# CANBed2040_V1_1.net
KiCad netlist of a schematic drawn in EAGLE
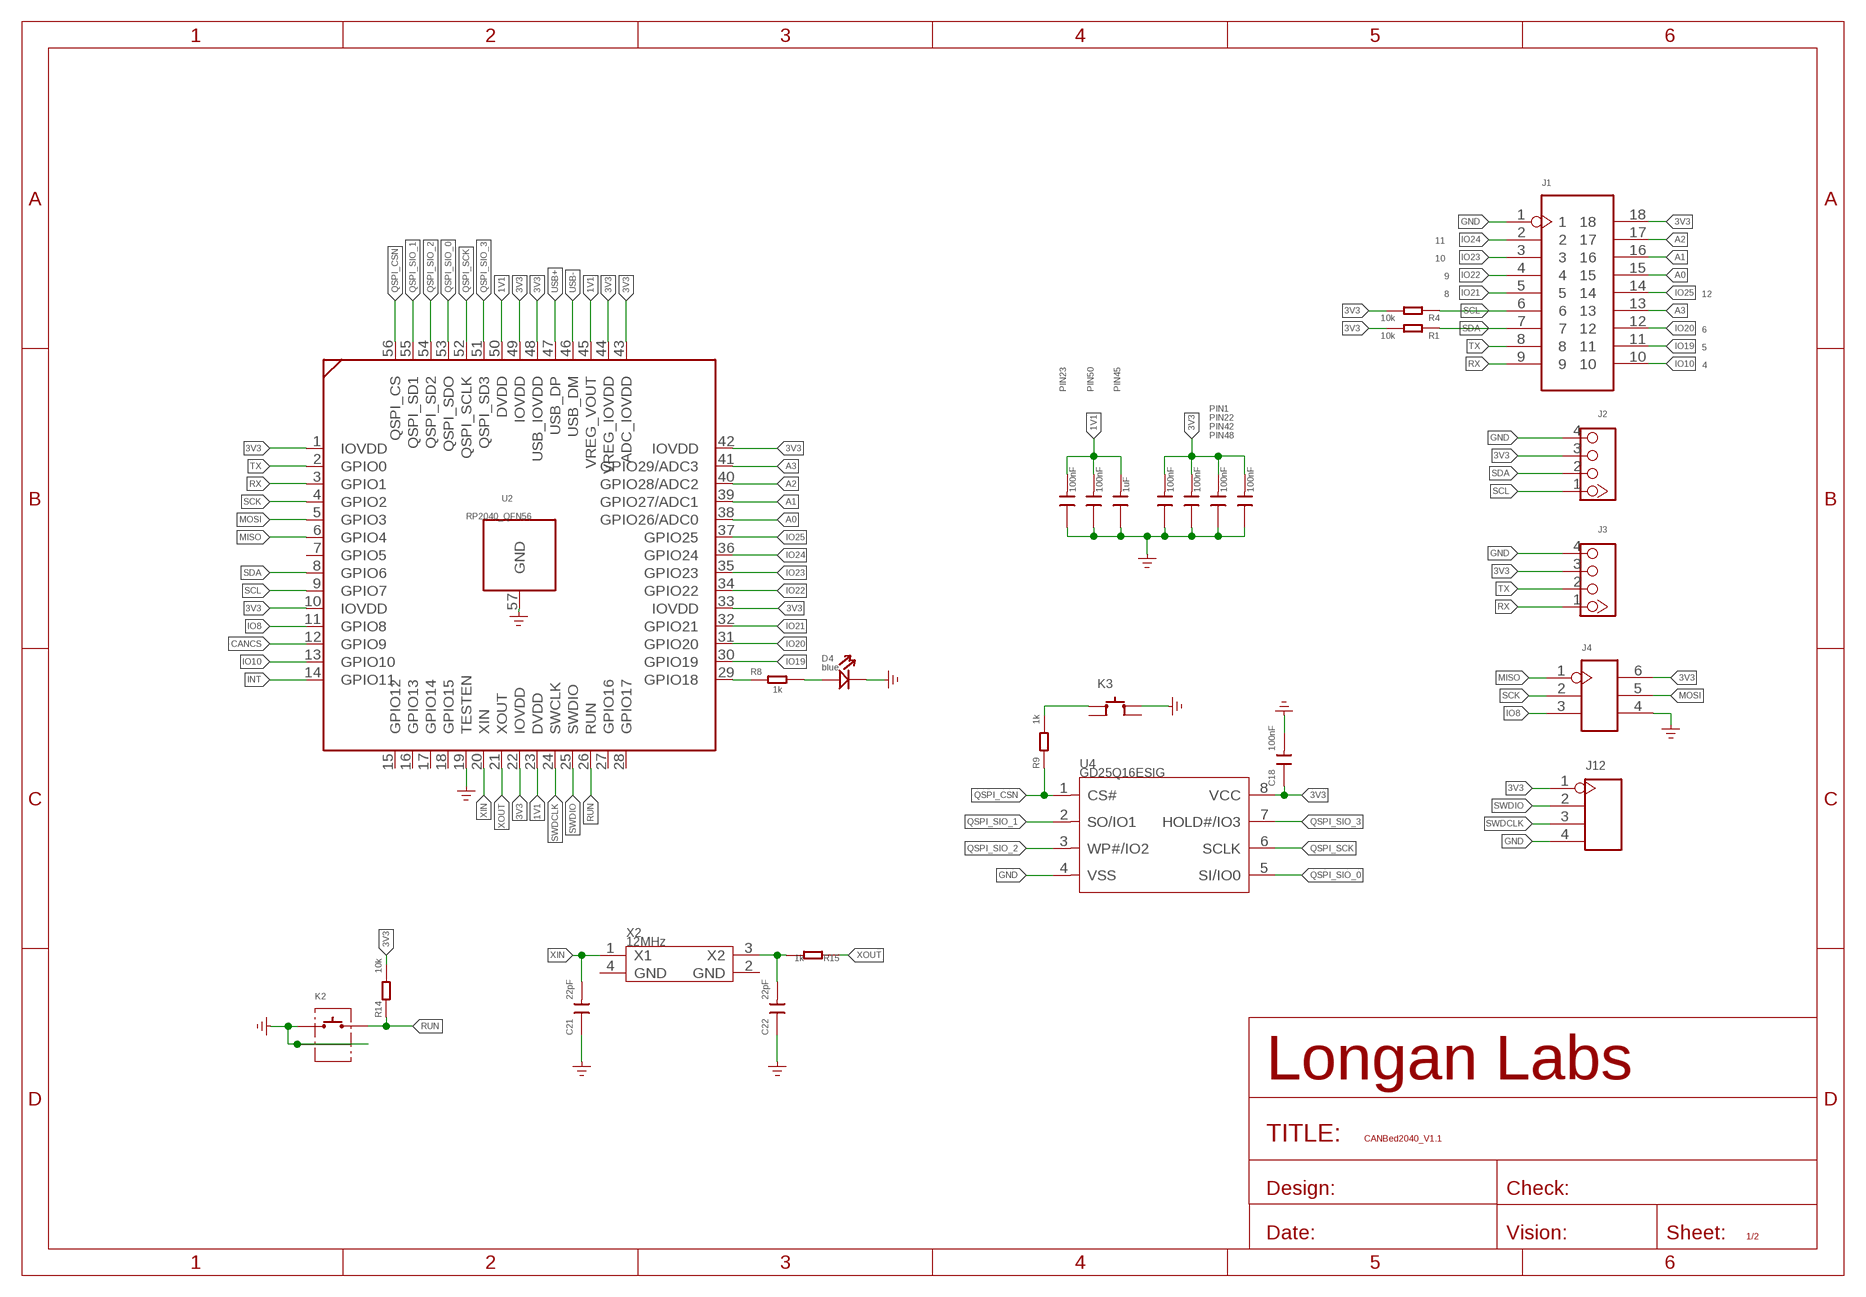
[diagram p0: schematic, sheet 1, part 1 of 2]
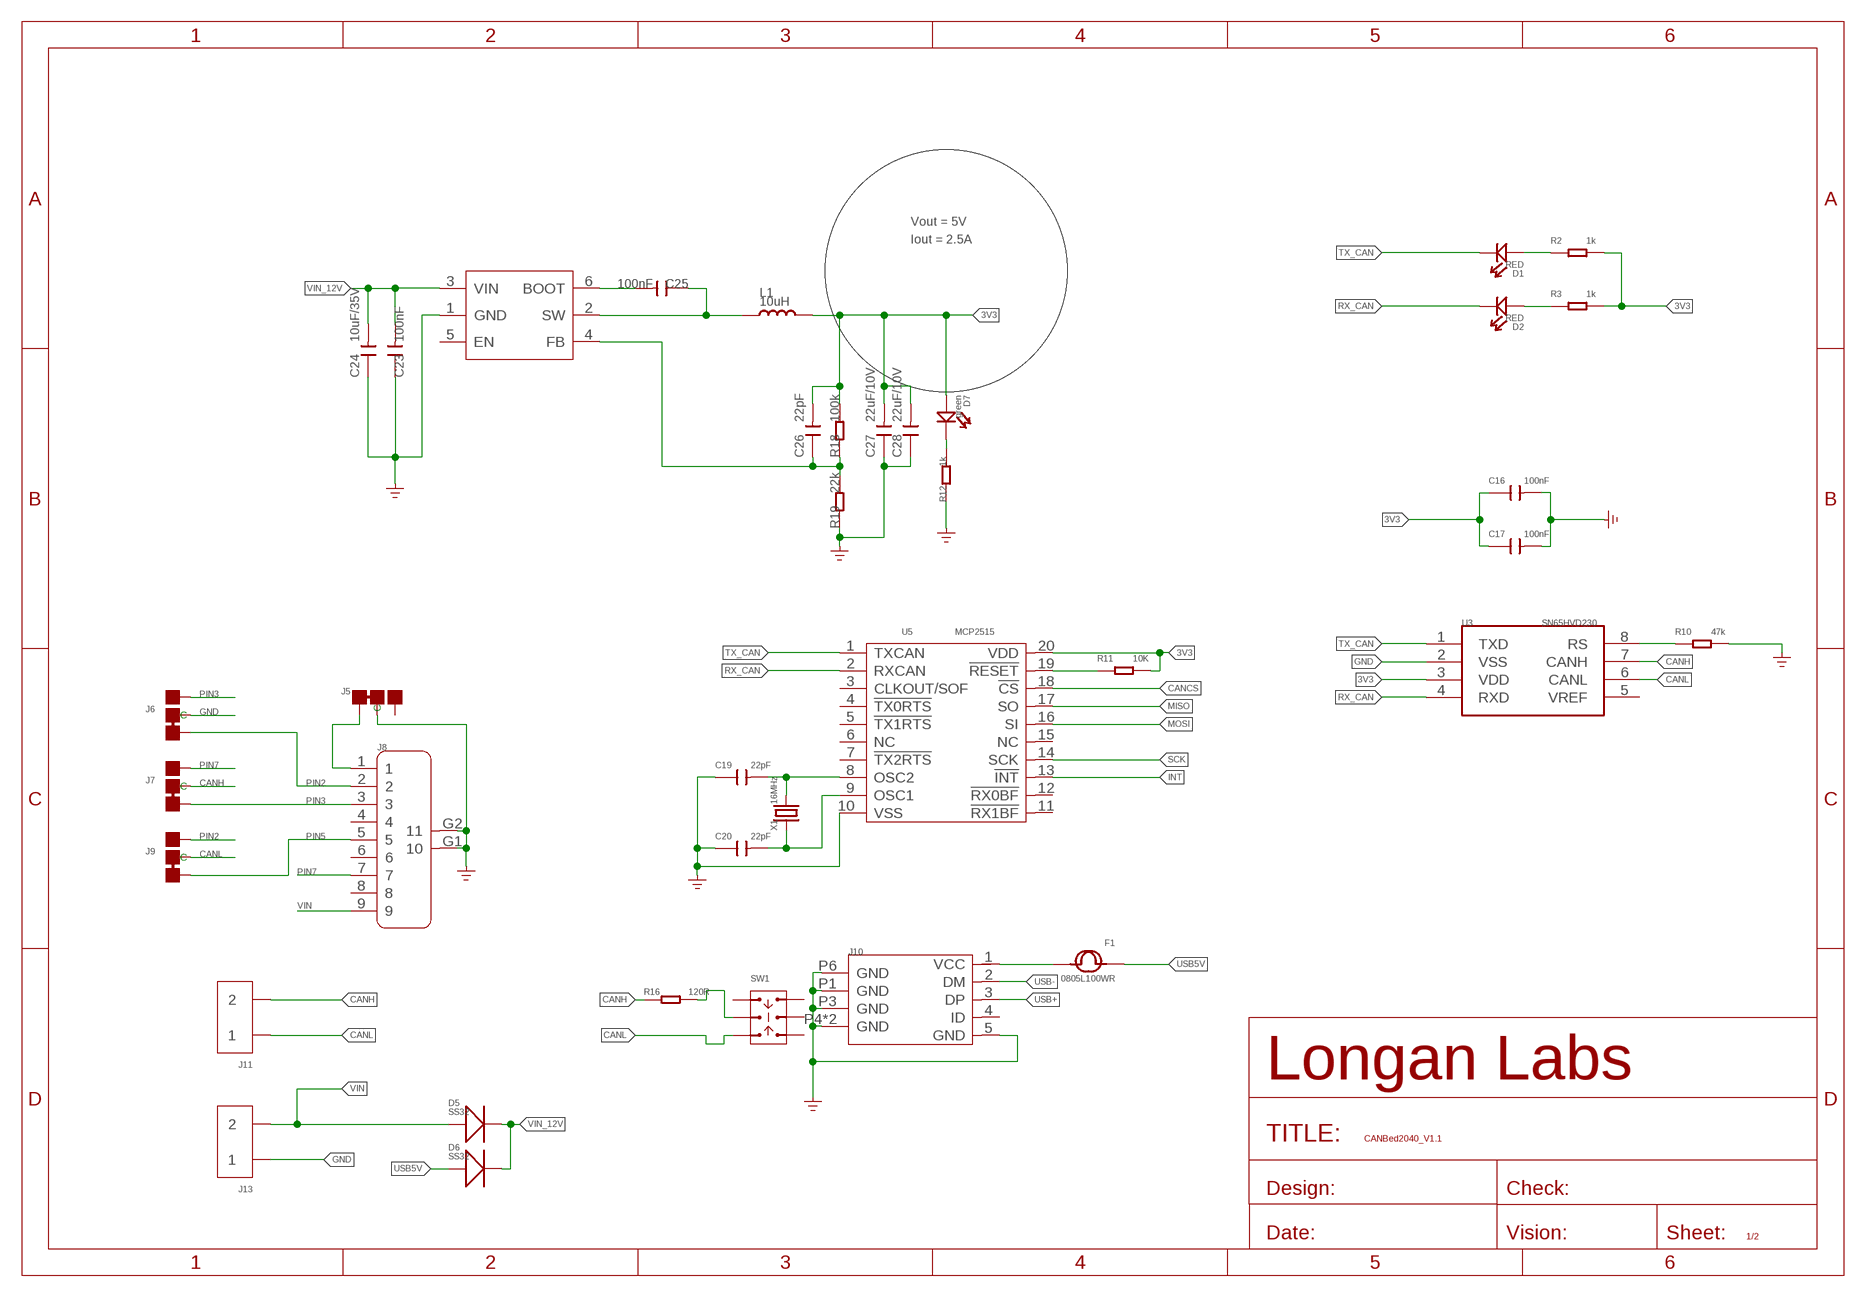
[diagram p1: schematic, sheet 1, part 2 of 2]

(export (version "E")
  (design (tool "Eeschema 10.0.6"))
  (components
    (comp (ref "C9")
      (value "100nF")
      (footprint "eagle-import:C0603")
      (libsource (lib "eagle-import") (part "CAP-0603"))
    )
    (comp (ref "C10")
      (value "100nF")
      (footprint "eagle-import:C0603")
      (libsource (lib "eagle-import") (part "CAP-0603"))
    )
    (comp (ref "C11")
      (value "1uF")
      (footprint "eagle-import:C0603")
      (libsource (lib "eagle-import") (part "CAP-0603"))
    )
    (comp (ref "C12")
      (value "100nF")
      (footprint "eagle-import:C0603")
      (libsource (lib "eagle-import") (part "CAP-0603"))
    )
    (comp (ref "C13")
      (value "100nF")
      (footprint "eagle-import:C0603")
      (libsource (lib "eagle-import") (part "CAP-0603"))
    )
    (comp (ref "C14")
      (value "100nF")
      (footprint "eagle-import:C0603")
      (libsource (lib "eagle-import") (part "CAP-0603"))
    )
    (comp (ref "C15")
      (value "100nF")
      (footprint "eagle-import:C0603")
      (libsource (lib "eagle-import") (part "CAP-0603"))
    )
    (comp (ref "C16")
      (value "100nF")
      (footprint "eagle-import:C0603")
      (libsource (lib "eagle-import") (part "CAP-0603"))
    )
    (comp (ref "C17")
      (value "100nF")
      (footprint "eagle-import:C0603")
      (libsource (lib "eagle-import") (part "CAP-0603"))
    )
    (comp (ref "C18")
      (value "100nF")
      (footprint "eagle-import:C0603")
      (libsource (lib "eagle-import") (part "CAP-0603"))
    )
    (comp (ref "C19")
      (value "22pF")
      (footprint "eagle-import:C0603")
      (libsource (lib "eagle-import") (part "CAP-0603"))
    )
    (comp (ref "C20")
      (value "22pF")
      (footprint "eagle-import:C0603")
      (libsource (lib "eagle-import") (part "CAP-0603"))
    )
    (comp (ref "C21")
      (value "22pF")
      (footprint "eagle-import:C0603")
      (libsource (lib "eagle-import") (part "CAP-0603"))
    )
    (comp (ref "C22")
      (value "22pF")
      (footprint "eagle-import:C0603")
      (libsource (lib "eagle-import") (part "CAP-0603"))
    )
    (comp (ref "C23")
      (value "100nF")
      (footprint "eagle-import:C0603")
      (libsource (lib "eagle-import") (part "CAP-0603"))
    )
    (comp (ref "C24")
      (value "10uF/35V")
      (footprint "eagle-import:C1206")
      (libsource (lib "eagle-import") (part "CAP-1206"))
    )
    (comp (ref "C25")
      (value "100nF")
      (footprint "eagle-import:C0603")
      (libsource (lib "eagle-import") (part "CAP-0603"))
    )
    (comp (ref "C26")
      (value "22pF")
      (footprint "eagle-import:C0603")
      (libsource (lib "eagle-import") (part "CAP-0603"))
    )
    (comp (ref "C27")
      (value "22uF/10V")
      (footprint "eagle-import:C0805")
      (libsource (lib "eagle-import") (part "CAP-0805"))
    )
    (comp (ref "C28")
      (value "22uF/10V")
      (footprint "eagle-import:C0805")
      (libsource (lib "eagle-import") (part "CAP-0805"))
    )
    (comp (ref "D1")
      (value "RED")
      (footprint "eagle-import:LED-0603")
      (libsource (lib "eagle-import") (part "LED'0603'"))
    )
    (comp (ref "D2")
      (value "RED")
      (footprint "eagle-import:LED-0603")
      (libsource (lib "eagle-import") (part "LED'0603'"))
    )
    (comp (ref "D4")
      (value "blue")
      (footprint "eagle-import:LED-0603")
      (libsource (lib "eagle-import") (part "LED'0603'"))
    )
    (comp (ref "D5")
      (value "SS32")
      (footprint "eagle-import:DO-214AC")
      (libsource (lib "eagle-import") (part "DIODE'SMA'"))
    )
    (comp (ref "D6")
      (value "SS32")
      (footprint "eagle-import:DO-214AC")
      (libsource (lib "eagle-import") (part "DIODE'SMA'"))
    )
    (comp (ref "D7")
      (value "green")
      (footprint "eagle-import:LED-0603")
      (libsource (lib "eagle-import") (part "LED'0603'"))
    )
    (comp (ref "F1")
      (value "0805L100WR")
      (footprint "eagle-import:F0805")
      (libsource (lib "eagle-import") (part "FUSE0805"))
    )
    (comp (ref "J1")
      (value "HEADER-2X9P-2.54")
      (footprint "eagle-import:H2X9-2.54")
      (libsource (lib "eagle-import") (part "HEADER-2X9P-2.54"))
    )
    (comp (ref "J2")
      (value "320110033")
      (footprint "eagle-import:HW4-2.0")
      (libsource (lib "eagle-import") (part "GROVE-CONNECTOR-DIP-2.0"))
    )
    (comp (ref "J3")
      (value "320110033")
      (footprint "eagle-import:HW4-2.0")
      (libsource (lib "eagle-import") (part "GROVE-CONNECTOR-DIP-2.0"))
    )
    (comp (ref "J4")
      (value "HEADER-2X3P-2.54")
      (footprint "eagle-import:H2X3-2.54")
      (libsource (lib "eagle-import") (part "HEADER-2X3P-2.54"))
    )
    (comp (ref "J5")
      (value "JUMPER-3P-SHORT")
      (footprint "eagle-import:3P-SMD-SHORT")
      (libsource (lib "eagle-import") (part "JUMPER-3P-SHORT"))
    )
    (comp (ref "J6")
      (value "JUMPER-3P-SHORT")
      (footprint "eagle-import:3P-SMD-SHORT")
      (libsource (lib "eagle-import") (part "JUMPER-3P-SHORT"))
    )
    (comp (ref "J7")
      (value "JUMPER-3P-SHORT")
      (footprint "eagle-import:3P-SMD-SHORT")
      (libsource (lib "eagle-import") (part "JUMPER-3P-SHORT"))
    )
    (comp (ref "J8")
      (value "DB9'MEAL'")
      (footprint "eagle-import:DB9-MEAL")
      (libsource (lib "eagle-import") (part "DB9'MEAL'"))
    )
    (comp (ref "J9")
      (value "JUMPER-3P-SHORT")
      (footprint "eagle-import:3P-SMD-SHORT")
      (libsource (lib "eagle-import") (part "JUMPER-3P-SHORT"))
    )
    (comp (ref "J10")
      (value "MICRO-USB5+4P-320010050")
      (footprint "eagle-import:MICRO-USB5+5P-SMD-0.65-7.2X5.06MM")
      (libsource (lib "eagle-import") (part "MICRO-USB5+4P-320010050"))
    )
    (comp (ref "J11")
      (value "SCREW-TERMINAL-2P'5.08'")
      (footprint "eagle-import:H2-5.0-10.5X8.0MM")
      (libsource (lib "eagle-import") (part "SCREW-TERMINAL-2P'5.08'"))
    )
    (comp (ref "J12")
      (value "HEADER-4P-65/35MIL")
      (footprint "eagle-import:H4-2.54")
      (libsource (lib "eagle-import") (part "HEADER-4P-65/35MIL"))
    )
    (comp (ref "J13")
      (value "SCREW-TERMINAL-2P'5.08'")
      (footprint "eagle-import:H2-5.0-10.5X8.0MM")
      (libsource (lib "eagle-import") (part "SCREW-TERMINAL-2P'5.08'"))
    )
    (comp (ref "K2")
      (value "BUTTON-2+2P")
      (footprint "eagle-import:SW2+2P-7.7X2.75X3.95MM")
      (libsource (lib "eagle-import") (part "BUTTON-2+2P"))
    )
    (comp (ref "K3")
      (value "BUTTON-4P-4.5X4.5X3.3MM")
      (footprint "eagle-import:SW4-4.5X4.5X3.3MM")
      (libsource (lib "eagle-import") (part "BUTTON-4P-4.5X4.5X3.3MM"))
    )
    (comp (ref "L1")
      (value "10uH")
      (footprint "eagle-import:L0420")
      (libsource (lib "eagle-import") (part "INDUCTOR-SPD3D16-4R7M"))
    )
    (comp (ref "R1")
      (value "10k")
      (footprint "eagle-import:R0603")
      (libsource (lib "eagle-import") (part "RES-0603"))
    )
    (comp (ref "R2")
      (value "1k")
      (footprint "eagle-import:R0603")
      (libsource (lib "eagle-import") (part "RES-0603"))
    )
    (comp (ref "R3")
      (value "1k")
      (footprint "eagle-import:R0603")
      (libsource (lib "eagle-import") (part "RES-0603"))
    )
    (comp (ref "R4")
      (value "10k")
      (footprint "eagle-import:R0603")
      (libsource (lib "eagle-import") (part "RES-0603"))
    )
    (comp (ref "R8")
      (value "1k")
      (footprint "eagle-import:R0603")
      (libsource (lib "eagle-import") (part "RES-0603"))
    )
    (comp (ref "R9")
      (value "1k")
      (footprint "eagle-import:R0603")
      (libsource (lib "eagle-import") (part "RES-0603"))
    )
    (comp (ref "R10")
      (value "47k")
      (footprint "eagle-import:R0603")
      (libsource (lib "eagle-import") (part "RES-0603"))
    )
    (comp (ref "R11")
      (value "10K")
      (footprint "eagle-import:R0603")
      (libsource (lib "eagle-import") (part "RES-0603"))
    )
    (comp (ref "R12")
      (value "1k")
      (footprint "eagle-import:R0603")
      (libsource (lib "eagle-import") (part "RES-0603"))
    )
    (comp (ref "R14")
      (value "10k")
      (footprint "eagle-import:R0603")
      (libsource (lib "eagle-import") (part "RES-0603"))
    )
    (comp (ref "R15")
      (value "1k")
      (footprint "eagle-import:R0603")
      (libsource (lib "eagle-import") (part "RES-0603"))
    )
    (comp (ref "R16")
      (value "120R")
      (footprint "eagle-import:R0603")
      (libsource (lib "eagle-import") (part "RES-0603"))
    )
    (comp (ref "R18")
      (value "100k")
      (footprint "eagle-import:R0603")
      (libsource (lib "eagle-import") (part "RES-0603"))
    )
    (comp (ref "R19")
      (value "22k")
      (footprint "eagle-import:R0603")
      (libsource (lib "eagle-import") (part "RES-0603"))
    )
    (comp (ref "SW1")
      (value "SWITCH-2CH-6P-311010004")
      (footprint "eagle-import:SW6-2.54-9.0X3.5X3.2+2.0MM")
      (libsource (lib "eagle-import") (part "SWITCH-2CH-6P-311010004"))
    )
    (comp (ref "U2")
      (value "RP2040_QFN56")
      (footprint "eagle-import:RP2040_QFN56")
      (libsource (lib "eagle-import") (part "RP2040_QFN56"))
    )
    (comp (ref "U3")
      (value "SN65HVD230")
      (footprint "eagle-import:SOIC8-6.0")
      (libsource (lib "eagle-import") (part "MCP2551-SOIC8"))
    )
    (comp (ref "U4")
      (value "GD25Q16ESIG")
      (footprint "eagle-import:SOP8-1.27-5.3X5.25X2MM")
      (libsource (lib "eagle-import") (part "FLASH-GD25Q16E"))
    )
    (comp (ref "U5")
      (value "MCP2515")
      (footprint "eagle-import:TSSOP20-0.65-6.5X4.4MM")
      (libsource (lib "eagle-import") (part "MCP2515'ST'"))
    )
    (comp (ref "U6")
      (value "PMIC-TPS54302")
      (footprint "eagle-import:SOT-23-6")
      (libsource (lib "eagle-import") (part "PMIC-TPS54302"))
    )
    (comp (ref "X1")
      (value "16MHz")
      (footprint "eagle-import:X4-SMD-3.2X2.5X0.7MM")
      (libsource (lib "eagle-import") (part "CRYSTAL-2P-3225"))
    )
    (comp (ref "X2")
      (value "12MHz")
      (footprint "eagle-import:X4-SMD-3.2X2.5X0.7MM")
      (libsource (lib "eagle-import") (part "CRYSTAL-4P-3225"))
    )
  )
  (nets
    (net (code "1") (name "1V1") (class "Default")
      (node (ref "C10") (pin "2") (pinfunction "2_2") (pintype "passive"))
      (node (ref "C11") (pin "2") (pinfunction "2_2") (pintype "passive"))
      (node (ref "C9") (pin "2") (pinfunction "2_2") (pintype "passive"))
      (node (ref "U2") (pin "23") (pinfunction "DVDD_23") (pintype "bidirectional"))
      (node (ref "U2") (pin "45") (pinfunction "VREG_VOUT_45") (pintype "bidirectional"))
      (node (ref "U2") (pin "50") (pinfunction "DVDD_50") (pintype "bidirectional"))
    )
    (net (code "2") (name "3V3") (class "Default")
      (node (ref "C12") (pin "2") (pinfunction "2_2") (pintype "passive"))
      (node (ref "C13") (pin "2") (pinfunction "2_2") (pintype "passive"))
      (node (ref "C14") (pin "2") (pinfunction "2_2") (pintype "passive"))
      (node (ref "C15") (pin "2") (pinfunction "2_2") (pintype "passive"))
      (node (ref "C16") (pin "1") (pinfunction "1_1") (pintype "passive"))
      (node (ref "C17") (pin "1") (pinfunction "1_1") (pintype "passive"))
      (node (ref "C18") (pin "1") (pinfunction "1_1") (pintype "passive"))
      (node (ref "C26") (pin "2") (pinfunction "2_2") (pintype "passive"))
      (node (ref "C27") (pin "2") (pinfunction "2_2") (pintype "passive"))
      (node (ref "C28") (pin "2") (pinfunction "2_2") (pintype "passive"))
      (node (ref "D7") (pin "+") (pinfunction "+_+") (pintype "passive"))
      (node (ref "J1") (pin "18") (pinfunction "18_18") (pintype "bidirectional"))
      (node (ref "J12") (pin "1") (pinfunction "P$1_1") (pintype "bidirectional"))
      (node (ref "J2") (pin "3") (pinfunction "3_3") (pintype "bidirectional"))
      (node (ref "J3") (pin "3") (pinfunction "3_3") (pintype "bidirectional"))
      (node (ref "J4") (pin "6") (pinfunction "6_6") (pintype "bidirectional"))
      (node (ref "L1") (pin "2") (pinfunction "2_2") (pintype "passive"))
      (node (ref "R1") (pin "2") (pinfunction "2_2") (pintype "passive"))
      (node (ref "R11") (pin "2") (pinfunction "2_2") (pintype "passive"))
      (node (ref "R14") (pin "2") (pinfunction "2_2") (pintype "passive"))
      (node (ref "R18") (pin "2") (pinfunction "2_2") (pintype "passive"))
      (node (ref "R2") (pin "2") (pinfunction "2_2") (pintype "passive"))
      (node (ref "R3") (pin "2") (pinfunction "2_2") (pintype "passive"))
      (node (ref "R4") (pin "2") (pinfunction "2_2") (pintype "passive"))
      (node (ref "U2") (pin "1") (pinfunction "IOVDD_1") (pintype "bidirectional"))
      (node (ref "U2") (pin "10") (pinfunction "IOVDD_10") (pintype "bidirectional"))
      (node (ref "U2") (pin "22") (pinfunction "IOVDD_22") (pintype "bidirectional"))
      (node (ref "U2") (pin "33") (pinfunction "IOVDD_33") (pintype "bidirectional"))
      (node (ref "U2") (pin "42") (pinfunction "IOVDD_42") (pintype "bidirectional"))
      (node (ref "U2") (pin "43") (pinfunction "ADC_IOVDD_43") (pintype "bidirectional"))
      (node (ref "U2") (pin "44") (pinfunction "VREG_IOVDD_44") (pintype "bidirectional"))
      (node (ref "U2") (pin "48") (pinfunction "USB_IOVDD_48") (pintype "bidirectional"))
      (node (ref "U2") (pin "49") (pinfunction "IOVDD_49") (pintype "bidirectional"))
      (node (ref "U3") (pin "3") (pinfunction "VDD_3") (pintype "bidirectional"))
      (node (ref "U4") (pin "8") (pinfunction "VCC_8") (pintype "bidirectional"))
      (node (ref "U5") (pin "20") (pinfunction "VDD_20") (pintype "bidirectional"))
    )
    (net (code "3") (name "A0") (class "Default")
      (node (ref "J1") (pin "15") (pinfunction "15_15") (pintype "bidirectional"))
      (node (ref "U2") (pin "38") (pinfunction "GPIO26/ADC0_38") (pintype "bidirectional"))
    )
    (net (code "4") (name "A1") (class "Default")
      (node (ref "J1") (pin "16") (pinfunction "16_16") (pintype "bidirectional"))
      (node (ref "U2") (pin "39") (pinfunction "GPIO27/ADC1_39") (pintype "bidirectional"))
    )
    (net (code "5") (name "A2") (class "Default")
      (node (ref "J1") (pin "17") (pinfunction "17_17") (pintype "bidirectional"))
      (node (ref "U2") (pin "40") (pinfunction "GPIO28/ADC2_40") (pintype "bidirectional"))
    )
    (net (code "6") (name "A3") (class "Default")
      (node (ref "J1") (pin "13") (pinfunction "13_13") (pintype "bidirectional"))
      (node (ref "U2") (pin "41") (pinfunction "GPIO29/ADC3_41") (pintype "bidirectional"))
    )
    (net (code "7") (name "CANCS") (class "Default")
      (node (ref "U2") (pin "12") (pinfunction "GPIO9_12") (pintype "bidirectional"))
      (node (ref "U5") (pin "18") (pinfunction "~{CS}_18") (pintype "bidirectional"))
    )
    (net (code "8") (name "CANH") (class "Default")
      (node (ref "J11") (pin "2") (pinfunction "2_2") (pintype "bidirectional"))
      (node (ref "J7") (pin "MM") (pinfunction "C_MM") (pintype "bidirectional"))
      (node (ref "R16") (pin "1") (pinfunction "1_1") (pintype "passive"))
      (node (ref "U3") (pin "7") (pinfunction "CANH_7") (pintype "bidirectional"))
    )
    (net (code "9") (name "CANL") (class "Default")
      (node (ref "J11") (pin "1") (pinfunction "1_1") (pintype "bidirectional"))
      (node (ref "J9") (pin "MM") (pinfunction "C_MM") (pintype "bidirectional"))
      (node (ref "SW1") (pin "CH1B") (pinfunction "CH1B_CH1B") (pintype "bidirectional"))
      (node (ref "U3") (pin "6") (pinfunction "CANL_6") (pintype "bidirectional"))
    )
    (net (code "10") (name "GND") (class "Default")
      (node (ref "C10") (pin "1") (pinfunction "1_1") (pintype "passive"))
      (node (ref "C11") (pin "1") (pinfunction "1_1") (pintype "passive"))
      (node (ref "C12") (pin "1") (pinfunction "1_1") (pintype "passive"))
      (node (ref "C13") (pin "1") (pinfunction "1_1") (pintype "passive"))
      (node (ref "C14") (pin "1") (pinfunction "1_1") (pintype "passive"))
      (node (ref "C15") (pin "1") (pinfunction "1_1") (pintype "passive"))
      (node (ref "C16") (pin "2") (pinfunction "2_2") (pintype "passive"))
      (node (ref "C17") (pin "2") (pinfunction "2_2") (pintype "passive"))
      (node (ref "C18") (pin "2") (pinfunction "2_2") (pintype "passive"))
      (node (ref "C19") (pin "1") (pinfunction "1_1") (pintype "passive"))
      (node (ref "C20") (pin "1") (pinfunction "1_1") (pintype "passive"))
      (node (ref "C21") (pin "1") (pinfunction "1_1") (pintype "passive"))
      (node (ref "C22") (pin "1") (pinfunction "1_1") (pintype "passive"))
      (node (ref "C23") (pin "1") (pinfunction "1_1") (pintype "passive"))
      (node (ref "C24") (pin "1") (pinfunction "1_1") (pintype "passive"))
      (node (ref "C27") (pin "1") (pinfunction "1_1") (pintype "passive"))
      (node (ref "C28") (pin "1") (pinfunction "1_1") (pintype "passive"))
      (node (ref "C9") (pin "1") (pinfunction "1_1") (pintype "passive"))
      (node (ref "D4") (pin "-") (pinfunction "-_-") (pintype "passive"))
      (node (ref "J1") (pin "1") (pinfunction "1_1") (pintype "bidirectional"))
      (node (ref "J10") (pin "5") (pinfunction "GND_5") (pintype "bidirectional"))
      (node (ref "J10") (pin "P1") (pinfunction "GND_P1") (pintype "bidirectional"))
      (node (ref "J10") (pin "P3") (pinfunction "GND_P3") (pintype "bidirectional"))
      (node (ref "J10") (pin "P4") (pinfunction "GND_P4") (pintype "bidirectional"))
      (node (ref "J10") (pin "P5") (pinfunction "GND_P5") (pintype "bidirectional"))
      (node (ref "J10") (pin "P6") (pinfunction "GND_P6") (pintype "bidirectional"))
      (node (ref "J12") (pin "4") (pinfunction "P$4_4") (pintype "bidirectional"))
      (node (ref "J13") (pin "1") (pinfunction "1_1") (pintype "bidirectional"))
      (node (ref "J2") (pin "4") (pinfunction "4_4") (pintype "bidirectional"))
      (node (ref "J3") (pin "4") (pinfunction "4_4") (pintype "bidirectional"))
      (node (ref "J4") (pin "4") (pinfunction "4_4") (pintype "bidirectional"))
      (node (ref "J5") (pin "MM") (pinfunction "C_MM") (pintype "bidirectional"))
      (node (ref "J6") (pin "MM") (pinfunction "C_MM") (pintype "bidirectional"))
      (node (ref "J8") (pin "G1") (pinfunction "10_G1") (pintype "bidirectional"))
      (node (ref "J8") (pin "G2") (pinfunction "11_G2") (pintype "bidirectional"))
      (node (ref "K2") (pin "1") (pinfunction "1_1") (pintype "bidirectional"))
      (node (ref "K2") (pin "S1") (pinfunction "S1_S1") (pintype "bidirectional"))
      (node (ref "K2") (pin "S2") (pinfunction "S2_S2") (pintype "bidirectional"))
      (node (ref "K3") (pin "3") (pinfunction "B0_3") (pintype "bidirectional"))
      (node (ref "R10") (pin "2") (pinfunction "2_2") (pintype "passive"))
      (node (ref "R12") (pin "1") (pinfunction "1_1") (pintype "passive"))
      (node (ref "R19") (pin "1") (pinfunction "1_1") (pintype "passive"))
      (node (ref "U2") (pin "19") (pinfunction "TESTEN_19") (pintype "bidirectional"))
      (node (ref "U2") (pin "57") (pinfunction "GND_57") (pintype "bidirectional"))
      (node (ref "U3") (pin "2") (pinfunction "VSS_2") (pintype "bidirectional"))
      (node (ref "U4") (pin "4") (pinfunction "VSS_4") (pintype "bidirectional"))
      (node (ref "U5") (pin "10") (pinfunction "VSS_10") (pintype "bidirectional"))
      (node (ref "U6") (pin "1") (pinfunction "GND_1") (pintype "bidirectional"))
    )
    (net (code "11") (name "INT") (class "Default")
      (node (ref "U2") (pin "14") (pinfunction "GPIO11_14") (pintype "bidirectional"))
      (node (ref "U5") (pin "13") (pinfunction "~{INT}_13") (pintype "bidirectional"))
    )
    (net (code "12") (name "IO8") (class "Default")
      (node (ref "J4") (pin "3") (pinfunction "3_3") (pintype "bidirectional"))
      (node (ref "U2") (pin "11") (pinfunction "GPIO8_11") (pintype "bidirectional"))
    )
    (net (code "13") (name "IO10") (class "Default")
      (node (ref "J1") (pin "10") (pinfunction "10_10") (pintype "bidirectional"))
      (node (ref "U2") (pin "13") (pinfunction "GPIO10_13") (pintype "bidirectional"))
    )
    (net (code "14") (name "IO19") (class "Default")
      (node (ref "J1") (pin "11") (pinfunction "11_11") (pintype "bidirectional"))
      (node (ref "U2") (pin "30") (pinfunction "GPIO19_30") (pintype "bidirectional"))
    )
    (net (code "15") (name "IO20") (class "Default")
      (node (ref "J1") (pin "12") (pinfunction "12_12") (pintype "bidirectional"))
      (node (ref "U2") (pin "31") (pinfunction "GPIO20_31") (pintype "bidirectional"))
    )
    (net (code "16") (name "IO21") (class "Default")
      (node (ref "J1") (pin "5") (pinfunction "5_5") (pintype "bidirectional"))
      (node (ref "U2") (pin "32") (pinfunction "GPIO21_32") (pintype "bidirectional"))
    )
    (net (code "17") (name "IO22") (class "Default")
      (node (ref "J1") (pin "4") (pinfunction "4_4") (pintype "bidirectional"))
      (node (ref "U2") (pin "34") (pinfunction "GPIO22_34") (pintype "bidirectional"))
    )
    (net (code "18") (name "IO23") (class "Default")
      (node (ref "J1") (pin "3") (pinfunction "3_3") (pintype "bidirectional"))
      (node (ref "U2") (pin "35") (pinfunction "GPIO23_35") (pintype "bidirectional"))
    )
    (net (code "19") (name "IO24") (class "Default")
      (node (ref "J1") (pin "2") (pinfunction "2_2") (pintype "bidirectional"))
      (node (ref "U2") (pin "36") (pinfunction "GPIO24_36") (pintype "bidirectional"))
    )
    (net (code "20") (name "IO25") (class "Default")
      (node (ref "J1") (pin "14") (pinfunction "14_14") (pintype "bidirectional"))
      (node (ref "U2") (pin "37") (pinfunction "GPIO25_37") (pintype "bidirectional"))
    )
    (net (code "21") (name "MISO") (class "Default")
      (node (ref "J4") (pin "1") (pinfunction "1_1") (pintype "bidirectional"))
      (node (ref "U2") (pin "6") (pinfunction "GPIO4_6") (pintype "bidirectional"))
      (node (ref "U5") (pin "17") (pinfunction "SO_17") (pintype "bidirectional"))
    )
    (net (code "22") (name "MOSI") (class "Default")
      (node (ref "J4") (pin "5") (pinfunction "5_5") (pintype "bidirectional"))
      (node (ref "U2") (pin "5") (pinfunction "GPIO3_5") (pintype "bidirectional"))
      (node (ref "U5") (pin "16") (pinfunction "SI_16") (pintype "bidirectional"))
    )
    (net (code "23") (name "Net-(D1-Pad+)") (class "Default")
      (node (ref "D1") (pin "+") (pinfunction "+_+") (pintype "passive"))
      (node (ref "R2") (pin "1") (pinfunction "1_1") (pintype "passive"))
    )
    (net (code "24") (name "Net-(D2-Pad+)") (class "Default")
      (node (ref "D2") (pin "+") (pinfunction "+_+") (pintype "passive"))
      (node (ref "R3") (pin "1") (pinfunction "1_1") (pintype "passive"))
    )
    (net (code "25") (name "Net-(D4-Pad+)") (class "Default")
      (node (ref "D4") (pin "+") (pinfunction "+_+") (pintype "passive"))
      (node (ref "R8") (pin "2") (pinfunction "2_2") (pintype "passive"))
    )
    (net (code "26") (name "Net-(D7-Pad-)") (class "Default")
      (node (ref "D7") (pin "-") (pinfunction "-_-") (pintype "passive"))
      (node (ref "R12") (pin "2") (pinfunction "2_2") (pintype "passive"))
    )
    (net (code "27") (name "Net-(J5-L)") (class "Default")
      (node (ref "J5") (pin "11") (pinfunction "L_11") (pintype "bidirectional"))
      (node (ref "J8") (pin "1") (pinfunction "1_1") (pintype "bidirectional"))
    )
    (net (code "28") (name "Net-(J10-VCC)") (class "Default")
      (node (ref "F1") (pin "2") (pinfunction "2_2") (pintype "bidirectional"))
      (node (ref "J10") (pin "1") (pinfunction "VCC_1") (pintype "bidirectional"))
    )
    (net (code "29") (name "Net-(K3-A0)") (class "Default")
      (node (ref "K3") (pin "1") (pinfunction "A0_1") (pintype "bidirectional"))
      (node (ref "R9") (pin "2") (pinfunction "2_2") (pintype "passive"))
    )
    (net (code "30") (name "Net-(R16-Pad2)") (class "Default")
      (node (ref "R16") (pin "2") (pinfunction "2_2") (pintype "passive"))
      (node (ref "SW1") (pin "COM1") (pinfunction "COM1_COM1") (pintype "bidirectional"))
    )
    (net (code "31") (name "Net-(U2-GPIO18)") (class "Default")
      (node (ref "R8") (pin "1") (pinfunction "1_1") (pintype "passive"))
      (node (ref "U2") (pin "29") (pinfunction "GPIO18_29") (pintype "bidirectional"))
    )
    (net (code "32") (name "Net-(U3-RS)") (class "Default")
      (node (ref "R10") (pin "1") (pinfunction "1_1") (pintype "passive"))
      (node (ref "U3") (pin "8") (pinfunction "RS_8") (pintype "bidirectional"))
    )
    (net (code "33") (name "Net-(U5-OSC1)") (class "Default")
      (node (ref "C20") (pin "2") (pinfunction "2_2") (pintype "passive"))
      (node (ref "U5") (pin "9") (pinfunction "OSC1_9") (pintype "bidirectional"))
      (node (ref "X1") (pin "1") (pinfunction "1_1") (pintype "passive"))
    )
    (net (code "34") (name "Net-(U5-OSC2)") (class "Default")
      (node (ref "C19") (pin "2") (pinfunction "2_2") (pintype "passive"))
      (node (ref "U5") (pin "8") (pinfunction "OSC2_8") (pintype "bidirectional"))
      (node (ref "X1") (pin "3") (pinfunction "2_3") (pintype "passive"))
    )
    (net (code "35") (name "Net-(U5-~{RESET})") (class "Default")
      (node (ref "R11") (pin "1") (pinfunction "1_1") (pintype "passive"))
      (node (ref "U5") (pin "19") (pinfunction "~{RESET}_19") (pintype "bidirectional"))
    )
    (net (code "36") (name "Net-(U6-BOOT)") (class "Default")
      (node (ref "C25") (pin "2") (pinfunction "2_2") (pintype "passive"))
      (node (ref "U6") (pin "6") (pinfunction "BOOT_6") (pintype "bidirectional"))
    )
    (net (code "37") (name "Net-(U6-FB)") (class "Default")
      (node (ref "C26") (pin "1") (pinfunction "1_1") (pintype "passive"))
      (node (ref "R18") (pin "1") (pinfunction "1_1") (pintype "passive"))
      (node (ref "R19") (pin "2") (pinfunction "2_2") (pintype "passive"))
      (node (ref "U6") (pin "4") (pinfunction "FB_4") (pintype "bidirectional"))
    )
    (net (code "38") (name "Net-(U6-SW)") (class "Default")
      (node (ref "C25") (pin "1") (pinfunction "1_1") (pintype "passive"))
      (node (ref "L1") (pin "1") (pinfunction "1_1") (pintype "passive"))
      (node (ref "U6") (pin "2") (pinfunction "SW_2") (pintype "bidirectional"))
    )
    (net (code "39") (name "Net-(X2-X2)") (class "Default")
      (node (ref "C22") (pin "2") (pinfunction "2_2") (pintype "passive"))
      (node (ref "R15") (pin "2") (pinfunction "2_2") (pintype "passive"))
      (node (ref "X2") (pin "3") (pinfunction "X2_3") (pintype "bidirectional"))
    )
    (net (code "40") (name "PIN2") (class "Default")
      (node (ref "J6") (pin "11") (pinfunction "L_11") (pintype "bidirectional"))
      (node (ref "J8") (pin "2") (pinfunction "2_2") (pintype "bidirectional"))
      (node (ref "J9") (pin "00") (pinfunction "R_00") (pintype "bidirectional"))
    )
    (net (code "41") (name "PIN3") (class "Default")
      (node (ref "J6") (pin "00") (pinfunction "R_00") (pintype "bidirectional"))
      (node (ref "J7") (pin "11") (pinfunction "L_11") (pintype "bidirectional"))
      (node (ref "J8") (pin "3") (pinfunction "3_3") (pintype "bidirectional"))
    )
    (net (code "42") (name "PIN5") (class "Default")
      (node (ref "J8") (pin "5") (pinfunction "5_5") (pintype "bidirectional"))
      (node (ref "J9") (pin "11") (pinfunction "L_11") (pintype "bidirectional"))
    )
    (net (code "43") (name "PIN7") (class "Default")
      (node (ref "J7") (pin "00") (pinfunction "R_00") (pintype "bidirectional"))
      (node (ref "J8") (pin "7") (pinfunction "7_7") (pintype "bidirectional"))
    )
    (net (code "44") (name "QSPI_CSN") (class "Default")
      (node (ref "R9") (pin "1") (pinfunction "1_1") (pintype "passive"))
      (node (ref "U2") (pin "56") (pinfunction "QSPI_CS_56") (pintype "bidirectional"))
      (node (ref "U4") (pin "1") (pinfunction "CS#_1") (pintype "bidirectional"))
    )
    (net (code "45") (name "QSPI_SCK") (class "Default")
      (node (ref "U2") (pin "52") (pinfunction "QSPI_SCLK_52") (pintype "bidirectional"))
      (node (ref "U4") (pin "6") (pinfunction "SCLK_6") (pintype "bidirectional"))
    )
    (net (code "46") (name "QSPI_SIO_0") (class "Default")
      (node (ref "U2") (pin "53") (pinfunction "QSPI_SDO_53") (pintype "bidirectional"))
      (node (ref "U4") (pin "5") (pinfunction "SI/IO0_5") (pintype "bidirectional"))
    )
    (net (code "47") (name "QSPI_SIO_1") (class "Default")
      (node (ref "U2") (pin "55") (pinfunction "QSPI_SD1_55") (pintype "bidirectional"))
      (node (ref "U4") (pin "2") (pinfunction "SO/IO1_2") (pintype "bidirectional"))
    )
    (net (code "48") (name "QSPI_SIO_2") (class "Default")
      (node (ref "U2") (pin "54") (pinfunction "QSPI_SD2_54") (pintype "bidirectional"))
      (node (ref "U4") (pin "3") (pinfunction "WP#/IO2_3") (pintype "bidirectional"))
    )
    (net (code "49") (name "QSPI_SIO_3") (class "Default")
      (node (ref "U2") (pin "51") (pinfunction "QSPI_SD3_51") (pintype "bidirectional"))
      (node (ref "U4") (pin "7") (pinfunction "HOLD#/IO3_7") (pintype "bidirectional"))
    )
    (net (code "50") (name "RUN") (class "Default")
      (node (ref "K2") (pin "2") (pinfunction "2_2") (pintype "bidirectional"))
      (node (ref "R14") (pin "1") (pinfunction "1_1") (pintype "passive"))
      (node (ref "U2") (pin "26") (pinfunction "RUN_26") (pintype "bidirectional"))
    )
    (net (code "51") (name "RX") (class "Default")
      (node (ref "J1") (pin "9") (pinfunction "9_9") (pintype "bidirectional"))
      (node (ref "J3") (pin "1") (pinfunction "1_1") (pintype "bidirectional"))
      (node (ref "U2") (pin "3") (pinfunction "GPIO1_3") (pintype "bidirectional"))
    )
    (net (code "52") (name "RX_CAN") (class "Default")
      (node (ref "D2") (pin "-") (pinfunction "-_-") (pintype "passive"))
      (node (ref "U3") (pin "4") (pinfunction "RXD_4") (pintype "bidirectional"))
      (node (ref "U5") (pin "2") (pinfunction "RXCAN_2") (pintype "bidirectional"))
    )
    (net (code "53") (name "SCK") (class "Default")
      (node (ref "J4") (pin "2") (pinfunction "2_2") (pintype "bidirectional"))
      (node (ref "U2") (pin "4") (pinfunction "GPIO2_4") (pintype "bidirectional"))
      (node (ref "U5") (pin "14") (pinfunction "SCK_14") (pintype "bidirectional"))
    )
    (net (code "54") (name "SCL") (class "Default")
      (node (ref "J1") (pin "6") (pinfunction "6_6") (pintype "bidirectional"))
      (node (ref "J2") (pin "1") (pinfunction "1_1") (pintype "bidirectional"))
      (node (ref "R4") (pin "1") (pinfunction "1_1") (pintype "passive"))
      (node (ref "U2") (pin "9") (pinfunction "GPIO7_9") (pintype "bidirectional"))
    )
    (net (code "55") (name "SDA") (class "Default")
      (node (ref "J1") (pin "7") (pinfunction "7_7") (pintype "bidirectional"))
      (node (ref "J2") (pin "2") (pinfunction "2_2") (pintype "bidirectional"))
      (node (ref "R1") (pin "1") (pinfunction "1_1") (pintype "passive"))
      (node (ref "U2") (pin "8") (pinfunction "GPIO6_8") (pintype "bidirectional"))
    )
    (net (code "56") (name "SWDCLK") (class "Default")
      (node (ref "J12") (pin "3") (pinfunction "P$3_3") (pintype "bidirectional"))
      (node (ref "U2") (pin "24") (pinfunction "SWCLK_24") (pintype "bidirectional"))
    )
    (net (code "57") (name "SWDIO") (class "Default")
      (node (ref "J12") (pin "2") (pinfunction "P$2_2") (pintype "bidirectional"))
      (node (ref "U2") (pin "25") (pinfunction "SWDIO_25") (pintype "bidirectional"))
    )
    (net (code "58") (name "TX") (class "Default")
      (node (ref "J1") (pin "8") (pinfunction "8_8") (pintype "bidirectional"))
      (node (ref "J3") (pin "2") (pinfunction "2_2") (pintype "bidirectional"))
      (node (ref "U2") (pin "2") (pinfunction "GPIO0_2") (pintype "bidirectional"))
    )
    (net (code "59") (name "TX_CAN") (class "Default")
      (node (ref "D1") (pin "-") (pinfunction "-_-") (pintype "passive"))
      (node (ref "U3") (pin "1") (pinfunction "TXD_1") (pintype "bidirectional"))
      (node (ref "U5") (pin "1") (pinfunction "TXCAN_1") (pintype "bidirectional"))
    )
    (net (code "60") (name "USB+") (class "Default")
      (node (ref "J10") (pin "3") (pinfunction "DP_3") (pintype "bidirectional"))
      (node (ref "U2") (pin "47") (pinfunction "USB_DP_47") (pintype "bidirectional"))
    )
    (net (code "61") (name "USB-") (class "Default")
      (node (ref "J10") (pin "2") (pinfunction "DM_2") (pintype "bidirectional"))
      (node (ref "U2") (pin "46") (pinfunction "USB_DM_46") (pintype "bidirectional"))
    )
    (net (code "62") (name "USB5V") (class "Default")
      (node (ref "D6") (pin "1") (pinfunction "+_1") (pintype "passive"))
      (node (ref "F1") (pin "1") (pinfunction "1_1") (pintype "bidirectional"))
    )
    (net (code "63") (name "VIN") (class "Default")
      (node (ref "D5") (pin "1") (pinfunction "+_1") (pintype "passive"))
      (node (ref "J13") (pin "2") (pinfunction "2_2") (pintype "bidirectional"))
      (node (ref "J8") (pin "9") (pinfunction "9_9") (pintype "bidirectional"))
    )
    (net (code "64") (name "VIN_12V") (class "Default")
      (node (ref "C23") (pin "2") (pinfunction "2_2") (pintype "passive"))
      (node (ref "C24") (pin "2") (pinfunction "2_2") (pintype "passive"))
      (node (ref "D5") (pin "2") (pinfunction "-_2") (pintype "passive"))
      (node (ref "D6") (pin "2") (pinfunction "-_2") (pintype "passive"))
      (node (ref "U6") (pin "3") (pinfunction "VIN_3") (pintype "bidirectional"))
    )
    (net (code "65") (name "XIN") (class "Default")
      (node (ref "C21") (pin "2") (pinfunction "2_2") (pintype "passive"))
      (node (ref "U2") (pin "20") (pinfunction "XIN_20") (pintype "bidirectional"))
      (node (ref "X2") (pin "1") (pinfunction "X1_1") (pintype "bidirectional"))
    )
    (net (code "66") (name "XOUT") (class "Default")
      (node (ref "R15") (pin "1") (pinfunction "1_1") (pintype "passive"))
      (node (ref "U2") (pin "21") (pinfunction "XOUT_21") (pintype "bidirectional"))
    )
    (net (code "67") (name "unconnected-(J5-R-Pad00)") (class "Default")
      (node (ref "J5") (pin "00") (pinfunction "R_00") (pintype "bidirectional"))
    )
    (net (code "68") (name "unconnected-(J8-Pad4)") (class "Default")
      (node (ref "J8") (pin "4") (pinfunction "4_4") (pintype "bidirectional"))
    )
    (net (code "69") (name "unconnected-(J8-Pad6)") (class "Default")
      (node (ref "J8") (pin "6") (pinfunction "6_6") (pintype "bidirectional"))
    )
    (net (code "70") (name "unconnected-(J8-Pad8)") (class "Default")
      (node (ref "J8") (pin "8") (pinfunction "8_8") (pintype "bidirectional"))
    )
    (net (code "71") (name "unconnected-(J10-ID-Pad4)") (class "Default")
      (node (ref "J10") (pin "4") (pinfunction "ID_4") (pintype "bidirectional"))
    )
    (net (code "72") (name "unconnected-(K3-A1-Pad2)") (class "Default")
      (node (ref "K3") (pin "2") (pinfunction "A1_2") (pintype "bidirectional"))
    )
    (net (code "73") (name "unconnected-(K3-B1-Pad4)") (class "Default")
      (node (ref "K3") (pin "4") (pinfunction "B1_4") (pintype "bidirectional"))
    )
    (net (code "74") (name "unconnected-(SW1-PadCH1A)") (class "Default")
      (node (ref "SW1") (pin "CH1A") (pinfunction "CH1A_CH1A") (pintype "bidirectional"))
    )
    (net (code "75") (name "unconnected-(SW1-PadCH2A)") (class "Default")
      (node (ref "SW1") (pin "CH2A") (pinfunction "CH2A_CH2A") (pintype "bidirectional"))
    )
    (net (code "76") (name "unconnected-(SW1-PadCH2B)") (class "Default")
      (node (ref "SW1") (pin "CH2B") (pinfunction "CH2B_CH2B") (pintype "bidirectional"))
    )
    (net (code "77") (name "unconnected-(SW1-PadCOM2)") (class "Default")
      (node (ref "SW1") (pin "COM2") (pinfunction "COM2_COM2") (pintype "bidirectional"))
    )
    (net (code "78") (name "unconnected-(U2-GPIO5-Pad7)") (class "Default")
      (node (ref "U2") (pin "7") (pinfunction "GPIO5_7") (pintype "bidirectional"))
    )
    (net (code "79") (name "unconnected-(U2-GPIO12-Pad15)") (class "Default")
      (node (ref "U2") (pin "15") (pinfunction "GPIO12_15") (pintype "bidirectional"))
    )
    (net (code "80") (name "unconnected-(U2-GPIO13-Pad16)") (class "Default")
      (node (ref "U2") (pin "16") (pinfunction "GPIO13_16") (pintype "bidirectional"))
    )
    (net (code "81") (name "unconnected-(U2-GPIO14-Pad17)") (class "Default")
      (node (ref "U2") (pin "17") (pinfunction "GPIO14_17") (pintype "bidirectional"))
    )
    (net (code "82") (name "unconnected-(U2-GPIO15-Pad18)") (class "Default")
      (node (ref "U2") (pin "18") (pinfunction "GPIO15_18") (pintype "bidirectional"))
    )
    (net (code "83") (name "unconnected-(U2-GPIO16-Pad27)") (class "Default")
      (node (ref "U2") (pin "27") (pinfunction "GPIO16_27") (pintype "bidirectional"))
    )
    (net (code "84") (name "unconnected-(U2-GPIO17-Pad28)") (class "Default")
      (node (ref "U2") (pin "28") (pinfunction "GPIO17_28") (pintype "bidirectional"))
    )
    (net (code "85") (name "unconnected-(U3-VREF-Pad5)") (class "Default")
      (node (ref "U3") (pin "5") (pinfunction "VREF_5") (pintype "bidirectional"))
    )
    (net (code "86") (name "unconnected-(U5-CLKOUT{slash}SOF-Pad3)") (class "Default")
      (node (ref "U5") (pin "3") (pinfunction "CLKOUT/SOF_3") (pintype "bidirectional"))
    )
    (net (code "87") (name "unconnected-(U5-NC-Pad6)") (class "Default")
      (node (ref "U5") (pin "6") (pinfunction "NC_6") (pintype "bidirectional"))
    )
    (net (code "88") (name "unconnected-(U5-NC-Pad15)") (class "Default")
      (node (ref "U5") (pin "15") (pinfunction "NC_15") (pintype "bidirectional"))
    )
    (net (code "89") (name "unconnected-(U5-~{RX0BF}-Pad12)") (class "Default")
      (node (ref "U5") (pin "12") (pinfunction "~{RX0BF}_12") (pintype "bidirectional"))
    )
    (net (code "90") (name "unconnected-(U5-~{RX1BF}-Pad11)") (class "Default")
      (node (ref "U5") (pin "11") (pinfunction "~{RX1BF}_11") (pintype "bidirectional"))
    )
    (net (code "91") (name "unconnected-(U5-~{TX0RTS}-Pad4)") (class "Default")
      (node (ref "U5") (pin "4") (pinfunction "~{TX0RTS}_4") (pintype "bidirectional"))
    )
    (net (code "92") (name "unconnected-(U5-~{TX1RTS}-Pad5)") (class "Default")
      (node (ref "U5") (pin "5") (pinfunction "~{TX1RTS}_5") (pintype "bidirectional"))
    )
    (net (code "93") (name "unconnected-(U5-~{TX2RTS}-Pad7)") (class "Default")
      (node (ref "U5") (pin "7") (pinfunction "~{TX2RTS}_7") (pintype "bidirectional"))
    )
    (net (code "94") (name "unconnected-(U6-EN-Pad5)") (class "Default")
      (node (ref "U6") (pin "5") (pinfunction "EN_5") (pintype "bidirectional"))
    )
    (net (code "95") (name "unconnected-(X2-GND-Pad2)") (class "Default")
      (node (ref "X2") (pin "2") (pinfunction "GND_2") (pintype "bidirectional"))
    )
    (net (code "96") (name "unconnected-(X2-GND-Pad4)") (class "Default")
      (node (ref "X2") (pin "4") (pinfunction "GND_4") (pintype "bidirectional"))
    )
  )
)
